# WVR_V1.net
KiCad netlist of a schematic drawn in EasyEDA
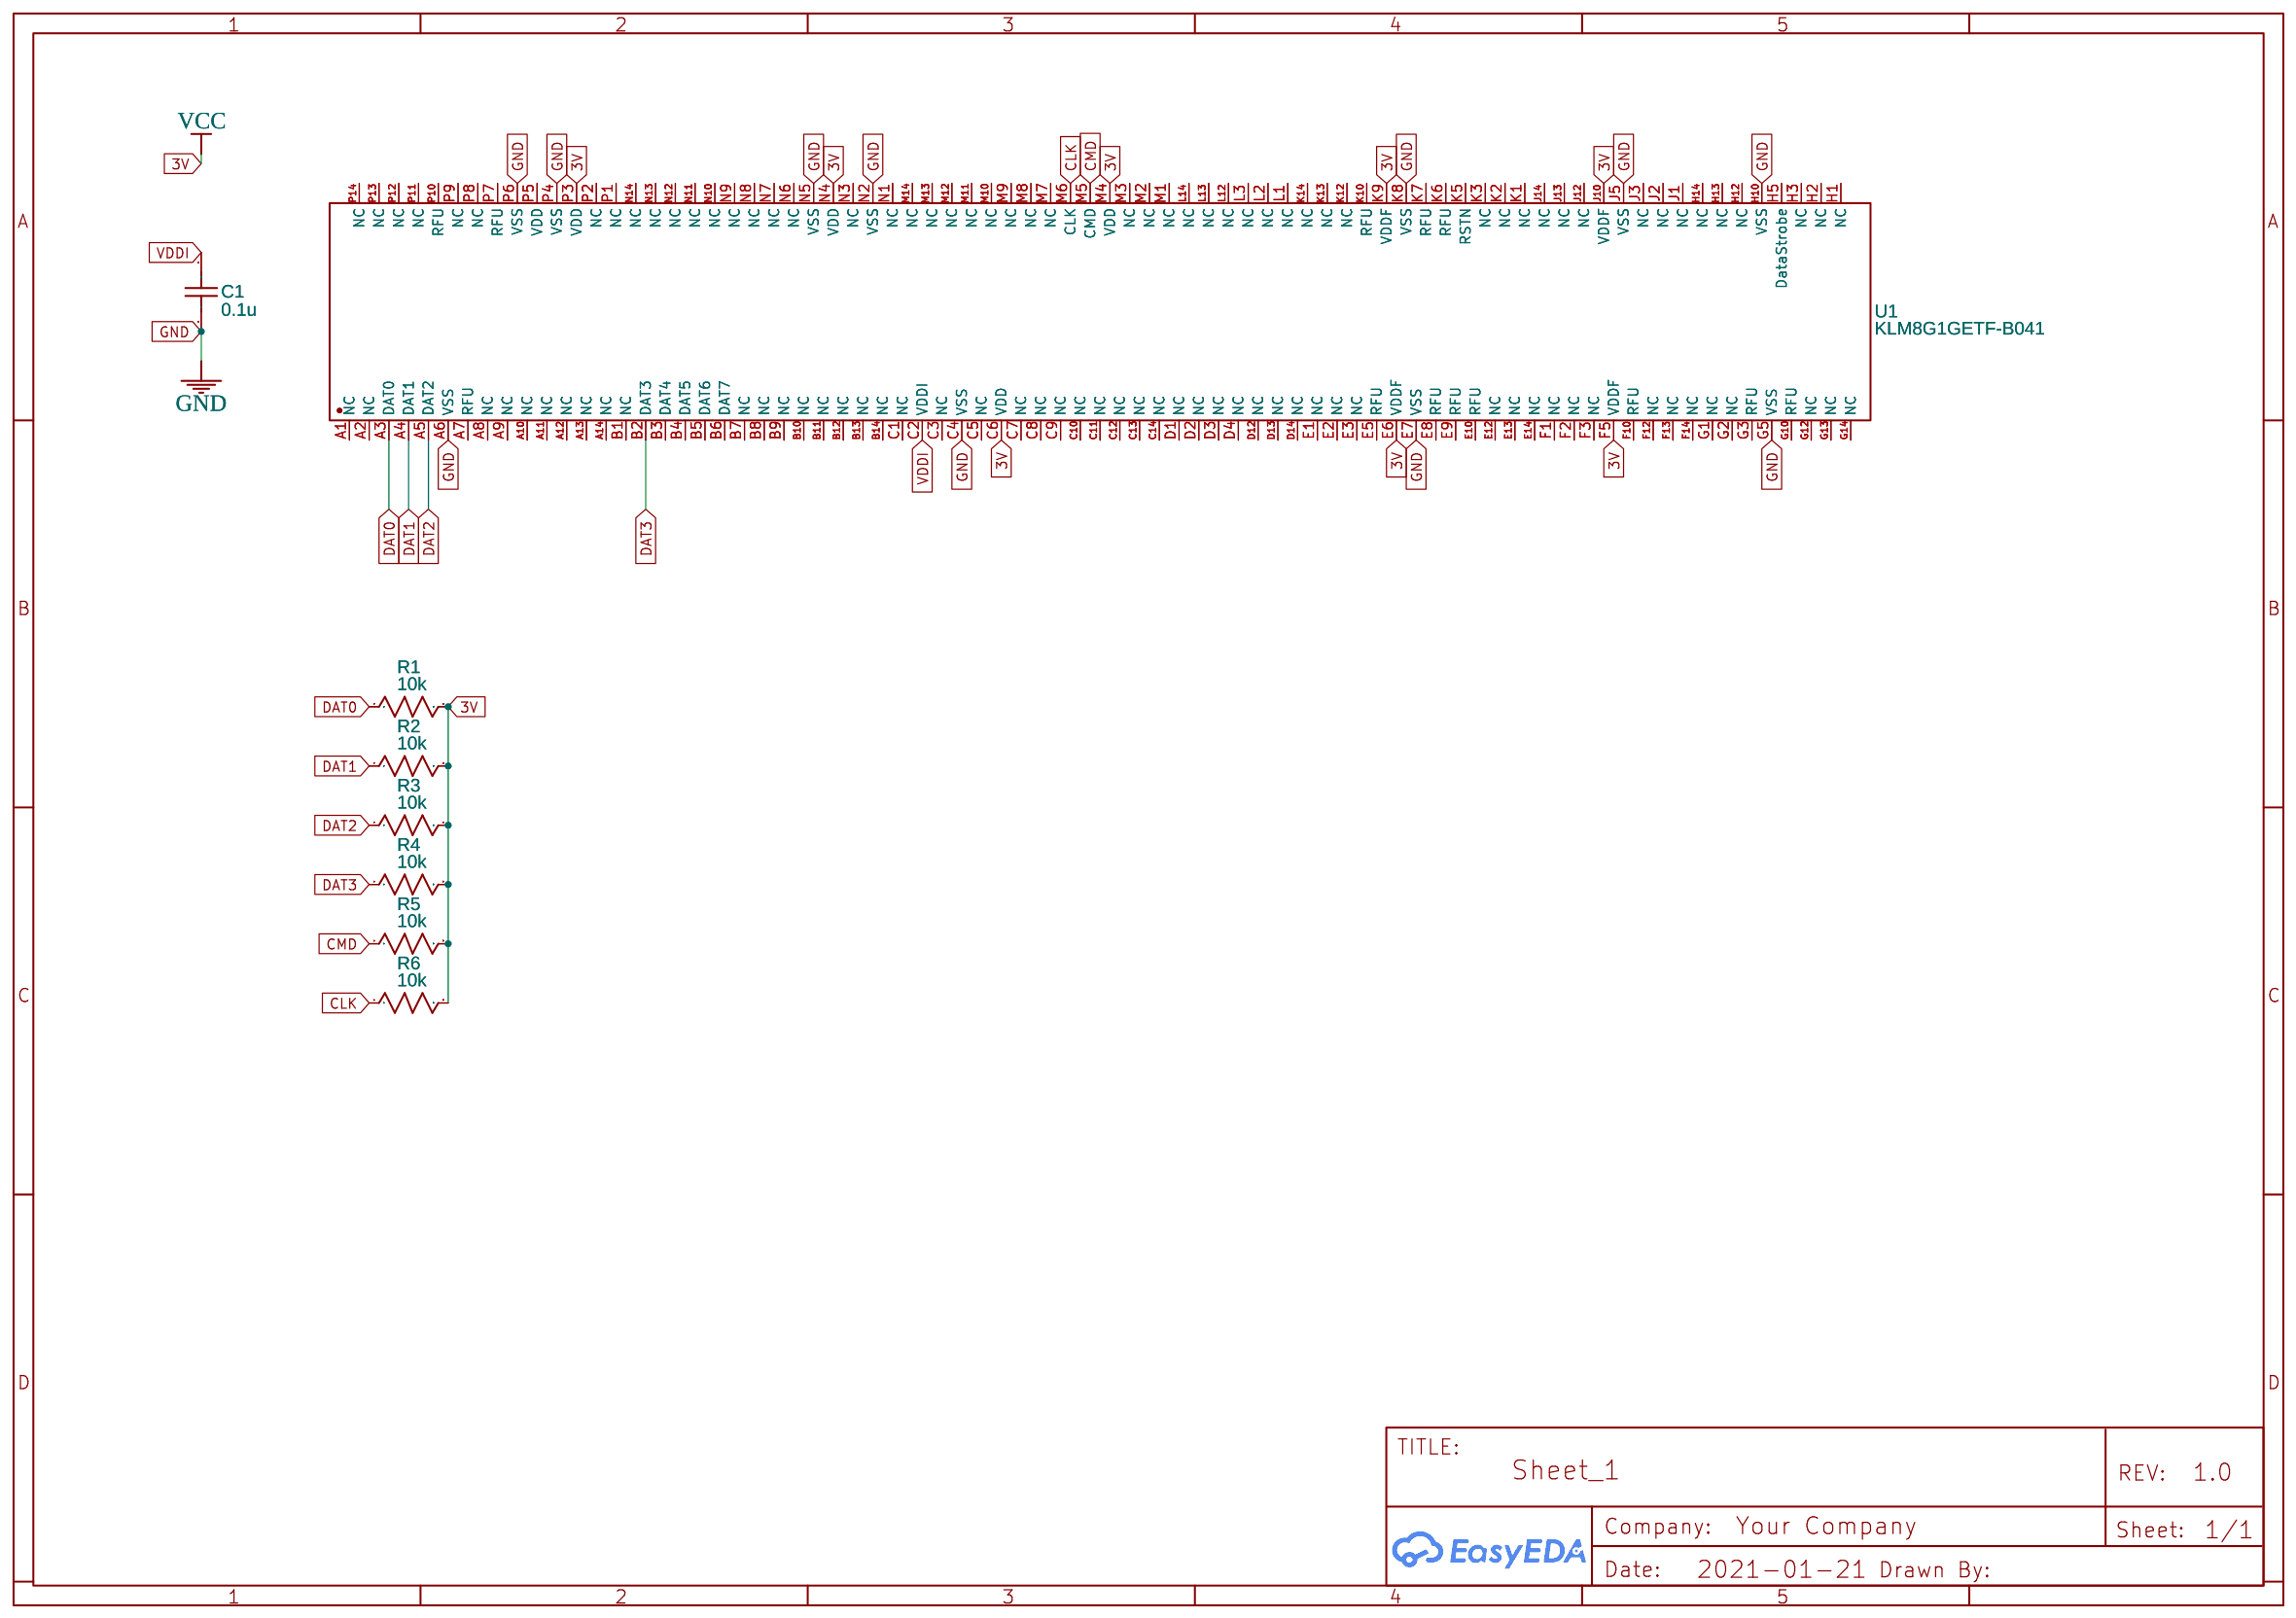
[diagram p0: schematic sheet]

(export (version "E")
  (design (tool "Eeschema 10.0.6"))
  (components
    (comp (ref "C1") (value "0.1u") (libsource (lib "") (part "C_0402_US")))
    (comp (ref "R1") (value "10k") (libsource (lib "") (part "R_0402_US")))
    (comp (ref "R2") (value "10k") (libsource (lib "") (part "R_0402_US")))
    (comp (ref "R3") (value "10k") (libsource (lib "") (part "R_0402_US")))
    (comp (ref "R4") (value "10k") (libsource (lib "") (part "R_0402_US")))
    (comp (ref "R5") (value "10k") (libsource (lib "") (part "R_0402_US")))
    (comp (ref "R6") (value "10k") (libsource (lib "") (part "R_0402_US")))
    (comp (ref "U1")
      (value "KLM8G1GETF-B041")
      (fields (field (name "BOM_Supplier Part") "C499918"))
      (libsource (lib "") (part "KLM8G1GETF-B041"))
    )
  )
  (nets
    (net (code "1") (name "3V") (class "Default")
      (node (ref "R1") (pin "2") (pinfunction "2_2") (pintype "unspecified"))
      (node (ref "R2") (pin "2") (pinfunction "2_2") (pintype "unspecified"))
      (node (ref "R3") (pin "2") (pinfunction "2_2") (pintype "unspecified"))
      (node (ref "R4") (pin "2") (pinfunction "2_2") (pintype "unspecified"))
      (node (ref "R5") (pin "2") (pinfunction "2_2") (pintype "unspecified"))
      (node (ref "R6") (pin "2") (pinfunction "2_2") (pintype "unspecified"))
      (node (ref "U1") (pin "C6") (pinfunction "VDD_C6") (pintype "unspecified"))
      (node (ref "U1") (pin "E6") (pinfunction "VDDF_E6") (pintype "unspecified"))
      (node (ref "U1") (pin "F5") (pinfunction "VDDF_F5") (pintype "unspecified"))
      (node (ref "U1") (pin "J10") (pinfunction "VDDF_J10") (pintype "unspecified"))
      (node (ref "U1") (pin "K9") (pinfunction "VDDF_K9") (pintype "unspecified"))
      (node (ref "U1") (pin "M4") (pinfunction "VDD_M4") (pintype "unspecified"))
      (node (ref "U1") (pin "N4") (pinfunction "VDD_N4") (pintype "unspecified"))
      (node (ref "U1") (pin "P3") (pinfunction "VDD_P3") (pintype "unspecified"))
    )
    (net (code "2") (name "CLK") (class "Default")
      (node (ref "R6") (pin "1") (pinfunction "1_1") (pintype "unspecified"))
      (node (ref "U1") (pin "M6") (pinfunction "CLK_M6") (pintype "unspecified"))
    )
    (net (code "3") (name "CMD") (class "Default")
      (node (ref "R5") (pin "1") (pinfunction "1_1") (pintype "unspecified"))
      (node (ref "U1") (pin "M5") (pinfunction "CMD_M5") (pintype "unspecified"))
    )
    (net (code "4") (name "DAT0") (class "Default")
      (node (ref "R1") (pin "1") (pinfunction "1_1") (pintype "unspecified"))
      (node (ref "U1") (pin "A3") (pinfunction "DAT0_A3") (pintype "unspecified"))
    )
    (net (code "5") (name "DAT1") (class "Default")
      (node (ref "R2") (pin "1") (pinfunction "1_1") (pintype "unspecified"))
      (node (ref "U1") (pin "A4") (pinfunction "DAT1_A4") (pintype "unspecified"))
    )
    (net (code "6") (name "DAT2") (class "Default")
      (node (ref "R3") (pin "1") (pinfunction "1_1") (pintype "unspecified"))
      (node (ref "U1") (pin "A5") (pinfunction "DAT2_A5") (pintype "unspecified"))
    )
    (net (code "7") (name "DAT3") (class "Default")
      (node (ref "R4") (pin "1") (pinfunction "1_1") (pintype "unspecified"))
      (node (ref "U1") (pin "B2") (pinfunction "DAT3_B2") (pintype "unspecified"))
    )
    (net (code "8") (name "GND") (class "Default")
      (node (ref "C1") (pin "1") (pinfunction "1_1") (pintype "unspecified"))
      (node (ref "U1") (pin "A6") (pinfunction "VSS_A6") (pintype "unspecified"))
      (node (ref "U1") (pin "C4") (pinfunction "VSS_C4") (pintype "unspecified"))
      (node (ref "U1") (pin "E7") (pinfunction "VSS_E7") (pintype "unspecified"))
      (node (ref "U1") (pin "G5") (pinfunction "VSS_G5") (pintype "unspecified"))
      (node (ref "U1") (pin "H10") (pinfunction "VSS_H10") (pintype "unspecified"))
      (node (ref "U1") (pin "J5") (pinfunction "VSS_J5") (pintype "unspecified"))
      (node (ref "U1") (pin "K8") (pinfunction "VSS_K8") (pintype "unspecified"))
      (node (ref "U1") (pin "N2") (pinfunction "VSS_N2") (pintype "unspecified"))
      (node (ref "U1") (pin "N5") (pinfunction "VSS_N5") (pintype "unspecified"))
      (node (ref "U1") (pin "P4") (pinfunction "VSS_P4") (pintype "unspecified"))
      (node (ref "U1") (pin "P6") (pinfunction "VSS_P6") (pintype "unspecified"))
    )
    (net (code "9") (name "VDDI") (class "Default")
      (node (ref "C1") (pin "2") (pinfunction "2_2") (pintype "unspecified"))
      (node (ref "U1") (pin "C2") (pinfunction "VDDI_C2") (pintype "unspecified"))
    )
    (net (code "10") (name "unconnected-(U1-DAT4-PadB3)") (class "Default")
      (node (ref "U1") (pin "B3") (pinfunction "DAT4_B3") (pintype "unspecified"))
    )
    (net (code "11") (name "unconnected-(U1-DAT5-PadB4)") (class "Default")
      (node (ref "U1") (pin "B4") (pinfunction "DAT5_B4") (pintype "unspecified"))
    )
    (net (code "12") (name "unconnected-(U1-DAT6-PadB5)") (class "Default")
      (node (ref "U1") (pin "B5") (pinfunction "DAT6_B5") (pintype "unspecified"))
    )
    (net (code "13") (name "unconnected-(U1-DAT7-PadB6)") (class "Default")
      (node (ref "U1") (pin "B6") (pinfunction "DAT7_B6") (pintype "unspecified"))
    )
    (net (code "14") (name "unconnected-(U1-DataStrobe-PadH5)") (class "Default")
      (node (ref "U1") (pin "H5") (pinfunction "DataStrobe_H5") (pintype "unspecified"))
    )
    (net (code "15") (name "unconnected-(U1-NC-PadA1)") (class "Default")
      (node (ref "U1") (pin "A1") (pinfunction "NC_A1") (pintype "unspecified"))
    )
    (net (code "16") (name "unconnected-(U1-NC-PadA2)") (class "Default")
      (node (ref "U1") (pin "A2") (pinfunction "NC_A2") (pintype "unspecified"))
    )
    (net (code "17") (name "unconnected-(U1-NC-PadA8)") (class "Default")
      (node (ref "U1") (pin "A8") (pinfunction "NC_A8") (pintype "unspecified"))
    )
    (net (code "18") (name "unconnected-(U1-NC-PadA9)") (class "Default")
      (node (ref "U1") (pin "A9") (pinfunction "NC_A9") (pintype "unspecified"))
    )
    (net (code "19") (name "unconnected-(U1-NC-PadA10)") (class "Default")
      (node (ref "U1") (pin "A10") (pinfunction "NC_A10") (pintype "unspecified"))
    )
    (net (code "20") (name "unconnected-(U1-NC-PadA11)") (class "Default")
      (node (ref "U1") (pin "A11") (pinfunction "NC_A11") (pintype "unspecified"))
    )
    (net (code "21") (name "unconnected-(U1-NC-PadA12)") (class "Default")
      (node (ref "U1") (pin "A12") (pinfunction "NC_A12") (pintype "unspecified"))
    )
    (net (code "22") (name "unconnected-(U1-NC-PadA13)") (class "Default")
      (node (ref "U1") (pin "A13") (pinfunction "NC_A13") (pintype "unspecified"))
    )
    (net (code "23") (name "unconnected-(U1-NC-PadA14)") (class "Default")
      (node (ref "U1") (pin "A14") (pinfunction "NC_A14") (pintype "unspecified"))
    )
    (net (code "24") (name "unconnected-(U1-NC-PadB1)") (class "Default")
      (node (ref "U1") (pin "B1") (pinfunction "NC_B1") (pintype "unspecified"))
    )
    (net (code "25") (name "unconnected-(U1-NC-PadB7)") (class "Default")
      (node (ref "U1") (pin "B7") (pinfunction "NC_B7") (pintype "unspecified"))
    )
    (net (code "26") (name "unconnected-(U1-NC-PadB8)") (class "Default")
      (node (ref "U1") (pin "B8") (pinfunction "NC_B8") (pintype "unspecified"))
    )
    (net (code "27") (name "unconnected-(U1-NC-PadB9)") (class "Default")
      (node (ref "U1") (pin "B9") (pinfunction "NC_B9") (pintype "unspecified"))
    )
    (net (code "28") (name "unconnected-(U1-NC-PadB10)") (class "Default")
      (node (ref "U1") (pin "B10") (pinfunction "NC_B10") (pintype "unspecified"))
    )
    (net (code "29") (name "unconnected-(U1-NC-PadB11)") (class "Default")
      (node (ref "U1") (pin "B11") (pinfunction "NC_B11") (pintype "unspecified"))
    )
    (net (code "30") (name "unconnected-(U1-NC-PadB12)") (class "Default")
      (node (ref "U1") (pin "B12") (pinfunction "NC_B12") (pintype "unspecified"))
    )
    (net (code "31") (name "unconnected-(U1-NC-PadB13)") (class "Default")
      (node (ref "U1") (pin "B13") (pinfunction "NC_B13") (pintype "unspecified"))
    )
    (net (code "32") (name "unconnected-(U1-NC-PadB14)") (class "Default")
      (node (ref "U1") (pin "B14") (pinfunction "NC_B14") (pintype "unspecified"))
    )
    (net (code "33") (name "unconnected-(U1-NC-PadC1)") (class "Default")
      (node (ref "U1") (pin "C1") (pinfunction "NC_C1") (pintype "unspecified"))
    )
    (net (code "34") (name "unconnected-(U1-NC-PadC3)") (class "Default")
      (node (ref "U1") (pin "C3") (pinfunction "NC_C3") (pintype "unspecified"))
    )
    (net (code "35") (name "unconnected-(U1-NC-PadC5)") (class "Default")
      (node (ref "U1") (pin "C5") (pinfunction "NC_C5") (pintype "unspecified"))
    )
    (net (code "36") (name "unconnected-(U1-NC-PadC7)") (class "Default")
      (node (ref "U1") (pin "C7") (pinfunction "NC_C7") (pintype "unspecified"))
    )
    (net (code "37") (name "unconnected-(U1-NC-PadC8)") (class "Default")
      (node (ref "U1") (pin "C8") (pinfunction "NC_C8") (pintype "unspecified"))
    )
    (net (code "38") (name "unconnected-(U1-NC-PadC9)") (class "Default")
      (node (ref "U1") (pin "C9") (pinfunction "NC_C9") (pintype "unspecified"))
    )
    (net (code "39") (name "unconnected-(U1-NC-PadC10)") (class "Default")
      (node (ref "U1") (pin "C10") (pinfunction "NC_C10") (pintype "unspecified"))
    )
    (net (code "40") (name "unconnected-(U1-NC-PadC11)") (class "Default")
      (node (ref "U1") (pin "C11") (pinfunction "NC_C11") (pintype "unspecified"))
    )
    (net (code "41") (name "unconnected-(U1-NC-PadC12)") (class "Default")
      (node (ref "U1") (pin "C12") (pinfunction "NC_C12") (pintype "unspecified"))
    )
    (net (code "42") (name "unconnected-(U1-NC-PadC13)") (class "Default")
      (node (ref "U1") (pin "C13") (pinfunction "NC_C13") (pintype "unspecified"))
    )
    (net (code "43") (name "unconnected-(U1-NC-PadC14)") (class "Default")
      (node (ref "U1") (pin "C14") (pinfunction "NC_C14") (pintype "unspecified"))
    )
    (net (code "44") (name "unconnected-(U1-NC-PadD1)") (class "Default")
      (node (ref "U1") (pin "D1") (pinfunction "NC_D1") (pintype "unspecified"))
    )
    (net (code "45") (name "unconnected-(U1-NC-PadD2)") (class "Default")
      (node (ref "U1") (pin "D2") (pinfunction "NC_D2") (pintype "unspecified"))
    )
    (net (code "46") (name "unconnected-(U1-NC-PadD3)") (class "Default")
      (node (ref "U1") (pin "D3") (pinfunction "NC_D3") (pintype "unspecified"))
    )
    (net (code "47") (name "unconnected-(U1-NC-PadD4)") (class "Default")
      (node (ref "U1") (pin "D4") (pinfunction "NC_D4") (pintype "unspecified"))
    )
    (net (code "48") (name "unconnected-(U1-NC-PadD12)") (class "Default")
      (node (ref "U1") (pin "D12") (pinfunction "NC_D12") (pintype "unspecified"))
    )
    (net (code "49") (name "unconnected-(U1-NC-PadD13)") (class "Default")
      (node (ref "U1") (pin "D13") (pinfunction "NC_D13") (pintype "unspecified"))
    )
    (net (code "50") (name "unconnected-(U1-NC-PadD14)") (class "Default")
      (node (ref "U1") (pin "D14") (pinfunction "NC_D14") (pintype "unspecified"))
    )
    (net (code "51") (name "unconnected-(U1-NC-PadE1)") (class "Default")
      (node (ref "U1") (pin "E1") (pinfunction "NC_E1") (pintype "unspecified"))
    )
    (net (code "52") (name "unconnected-(U1-NC-PadE2)") (class "Default")
      (node (ref "U1") (pin "E2") (pinfunction "NC_E2") (pintype "unspecified"))
    )
    (net (code "53") (name "unconnected-(U1-NC-PadE3)") (class "Default")
      (node (ref "U1") (pin "E3") (pinfunction "NC_E3") (pintype "unspecified"))
    )
    (net (code "54") (name "unconnected-(U1-NC-PadE12)") (class "Default")
      (node (ref "U1") (pin "E12") (pinfunction "NC_E12") (pintype "unspecified"))
    )
    (net (code "55") (name "unconnected-(U1-NC-PadE13)") (class "Default")
      (node (ref "U1") (pin "E13") (pinfunction "NC_E13") (pintype "unspecified"))
    )
    (net (code "56") (name "unconnected-(U1-NC-PadE14)") (class "Default")
      (node (ref "U1") (pin "E14") (pinfunction "NC_E14") (pintype "unspecified"))
    )
    (net (code "57") (name "unconnected-(U1-NC-PadF1)") (class "Default")
      (node (ref "U1") (pin "F1") (pinfunction "NC_F1") (pintype "unspecified"))
    )
    (net (code "58") (name "unconnected-(U1-NC-PadF2)") (class "Default")
      (node (ref "U1") (pin "F2") (pinfunction "NC_F2") (pintype "unspecified"))
    )
    (net (code "59") (name "unconnected-(U1-NC-PadF3)") (class "Default")
      (node (ref "U1") (pin "F3") (pinfunction "NC_F3") (pintype "unspecified"))
    )
    (net (code "60") (name "unconnected-(U1-NC-PadF12)") (class "Default")
      (node (ref "U1") (pin "F12") (pinfunction "NC_F12") (pintype "unspecified"))
    )
    (net (code "61") (name "unconnected-(U1-NC-PadF13)") (class "Default")
      (node (ref "U1") (pin "F13") (pinfunction "NC_F13") (pintype "unspecified"))
    )
    (net (code "62") (name "unconnected-(U1-NC-PadF14)") (class "Default")
      (node (ref "U1") (pin "F14") (pinfunction "NC_F14") (pintype "unspecified"))
    )
    (net (code "63") (name "unconnected-(U1-NC-PadG1)") (class "Default")
      (node (ref "U1") (pin "G1") (pinfunction "NC_G1") (pintype "unspecified"))
    )
    (net (code "64") (name "unconnected-(U1-NC-PadG2)") (class "Default")
      (node (ref "U1") (pin "G2") (pinfunction "NC_G2") (pintype "unspecified"))
    )
    (net (code "65") (name "unconnected-(U1-NC-PadG12)") (class "Default")
      (node (ref "U1") (pin "G12") (pinfunction "NC_G12") (pintype "unspecified"))
    )
    (net (code "66") (name "unconnected-(U1-NC-PadG13)") (class "Default")
      (node (ref "U1") (pin "G13") (pinfunction "NC_G13") (pintype "unspecified"))
    )
    (net (code "67") (name "unconnected-(U1-NC-PadG14)") (class "Default")
      (node (ref "U1") (pin "G14") (pinfunction "NC_G14") (pintype "unspecified"))
    )
    (net (code "68") (name "unconnected-(U1-NC-PadH1)") (class "Default")
      (node (ref "U1") (pin "H1") (pinfunction "NC_H1") (pintype "unspecified"))
    )
    (net (code "69") (name "unconnected-(U1-NC-PadH2)") (class "Default")
      (node (ref "U1") (pin "H2") (pinfunction "NC_H2") (pintype "unspecified"))
    )
    (net (code "70") (name "unconnected-(U1-NC-PadH3)") (class "Default")
      (node (ref "U1") (pin "H3") (pinfunction "NC_H3") (pintype "unspecified"))
    )
    (net (code "71") (name "unconnected-(U1-NC-PadH12)") (class "Default")
      (node (ref "U1") (pin "H12") (pinfunction "NC_H12") (pintype "unspecified"))
    )
    (net (code "72") (name "unconnected-(U1-NC-PadH13)") (class "Default")
      (node (ref "U1") (pin "H13") (pinfunction "NC_H13") (pintype "unspecified"))
    )
    (net (code "73") (name "unconnected-(U1-NC-PadH14)") (class "Default")
      (node (ref "U1") (pin "H14") (pinfunction "NC_H14") (pintype "unspecified"))
    )
    (net (code "74") (name "unconnected-(U1-NC-PadJ1)") (class "Default")
      (node (ref "U1") (pin "J1") (pinfunction "NC_J1") (pintype "unspecified"))
    )
    (net (code "75") (name "unconnected-(U1-NC-PadJ2)") (class "Default")
      (node (ref "U1") (pin "J2") (pinfunction "NC_J2") (pintype "unspecified"))
    )
    (net (code "76") (name "unconnected-(U1-NC-PadJ3)") (class "Default")
      (node (ref "U1") (pin "J3") (pinfunction "NC_J3") (pintype "unspecified"))
    )
    (net (code "77") (name "unconnected-(U1-NC-PadJ12)") (class "Default")
      (node (ref "U1") (pin "J12") (pinfunction "NC_J12") (pintype "unspecified"))
    )
    (net (code "78") (name "unconnected-(U1-NC-PadJ13)") (class "Default")
      (node (ref "U1") (pin "J13") (pinfunction "NC_J13") (pintype "unspecified"))
    )
    (net (code "79") (name "unconnected-(U1-NC-PadJ14)") (class "Default")
      (node (ref "U1") (pin "J14") (pinfunction "NC_J14") (pintype "unspecified"))
    )
    (net (code "80") (name "unconnected-(U1-NC-PadK1)") (class "Default")
      (node (ref "U1") (pin "K1") (pinfunction "NC_K1") (pintype "unspecified"))
    )
    (net (code "81") (name "unconnected-(U1-NC-PadK2)") (class "Default")
      (node (ref "U1") (pin "K2") (pinfunction "NC_K2") (pintype "unspecified"))
    )
    (net (code "82") (name "unconnected-(U1-NC-PadK3)") (class "Default")
      (node (ref "U1") (pin "K3") (pinfunction "NC_K3") (pintype "unspecified"))
    )
    (net (code "83") (name "unconnected-(U1-NC-PadK12)") (class "Default")
      (node (ref "U1") (pin "K12") (pinfunction "NC_K12") (pintype "unspecified"))
    )
    (net (code "84") (name "unconnected-(U1-NC-PadK13)") (class "Default")
      (node (ref "U1") (pin "K13") (pinfunction "NC_K13") (pintype "unspecified"))
    )
    (net (code "85") (name "unconnected-(U1-NC-PadK14)") (class "Default")
      (node (ref "U1") (pin "K14") (pinfunction "NC_K14") (pintype "unspecified"))
    )
    (net (code "86") (name "unconnected-(U1-NC-PadL1)") (class "Default")
      (node (ref "U1") (pin "L1") (pinfunction "NC_L1") (pintype "unspecified"))
    )
    (net (code "87") (name "unconnected-(U1-NC-PadL2)") (class "Default")
      (node (ref "U1") (pin "L2") (pinfunction "NC_L2") (pintype "unspecified"))
    )
    (net (code "88") (name "unconnected-(U1-NC-PadL3)") (class "Default")
      (node (ref "U1") (pin "L3") (pinfunction "NC_L3") (pintype "unspecified"))
    )
    (net (code "89") (name "unconnected-(U1-NC-PadL12)") (class "Default")
      (node (ref "U1") (pin "L12") (pinfunction "NC_L12") (pintype "unspecified"))
    )
    (net (code "90") (name "unconnected-(U1-NC-PadL13)") (class "Default")
      (node (ref "U1") (pin "L13") (pinfunction "NC_L13") (pintype "unspecified"))
    )
    (net (code "91") (name "unconnected-(U1-NC-PadL14)") (class "Default")
      (node (ref "U1") (pin "L14") (pinfunction "NC_L14") (pintype "unspecified"))
    )
    (net (code "92") (name "unconnected-(U1-NC-PadM1)") (class "Default")
      (node (ref "U1") (pin "M1") (pinfunction "NC_M1") (pintype "unspecified"))
    )
    (net (code "93") (name "unconnected-(U1-NC-PadM2)") (class "Default")
      (node (ref "U1") (pin "M2") (pinfunction "NC_M2") (pintype "unspecified"))
    )
    (net (code "94") (name "unconnected-(U1-NC-PadM3)") (class "Default")
      (node (ref "U1") (pin "M3") (pinfunction "NC_M3") (pintype "unspecified"))
    )
    (net (code "95") (name "unconnected-(U1-NC-PadM7)") (class "Default")
      (node (ref "U1") (pin "M7") (pinfunction "NC_M7") (pintype "unspecified"))
    )
    (net (code "96") (name "unconnected-(U1-NC-PadM8)") (class "Default")
      (node (ref "U1") (pin "M8") (pinfunction "NC_M8") (pintype "unspecified"))
    )
    (net (code "97") (name "unconnected-(U1-NC-PadM9)") (class "Default")
      (node (ref "U1") (pin "M9") (pinfunction "NC_M9") (pintype "unspecified"))
    )
    (net (code "98") (name "unconnected-(U1-NC-PadM10)") (class "Default")
      (node (ref "U1") (pin "M10") (pinfunction "NC_M10") (pintype "unspecified"))
    )
    (net (code "99") (name "unconnected-(U1-NC-PadM11)") (class "Default")
      (node (ref "U1") (pin "M11") (pinfunction "NC_M11") (pintype "unspecified"))
    )
    (net (code "100") (name "unconnected-(U1-NC-PadM12)") (class "Default")
      (node (ref "U1") (pin "M12") (pinfunction "NC_M12") (pintype "unspecified"))
    )
    (net (code "101") (name "unconnected-(U1-NC-PadM13)") (class "Default")
      (node (ref "U1") (pin "M13") (pinfunction "NC_M13") (pintype "unspecified"))
    )
    (net (code "102") (name "unconnected-(U1-NC-PadM14)") (class "Default")
      (node (ref "U1") (pin "M14") (pinfunction "NC_M14") (pintype "unspecified"))
    )
    (net (code "103") (name "unconnected-(U1-NC-PadN1)") (class "Default")
      (node (ref "U1") (pin "N1") (pinfunction "NC_N1") (pintype "unspecified"))
    )
    (net (code "104") (name "unconnected-(U1-NC-PadN3)") (class "Default")
      (node (ref "U1") (pin "N3") (pinfunction "NC_N3") (pintype "unspecified"))
    )
    (net (code "105") (name "unconnected-(U1-NC-PadN6)") (class "Default")
      (node (ref "U1") (pin "N6") (pinfunction "NC_N6") (pintype "unspecified"))
    )
    (net (code "106") (name "unconnected-(U1-NC-PadN7)") (class "Default")
      (node (ref "U1") (pin "N7") (pinfunction "NC_N7") (pintype "unspecified"))
    )
    (net (code "107") (name "unconnected-(U1-NC-PadN8)") (class "Default")
      (node (ref "U1") (pin "N8") (pinfunction "NC_N8") (pintype "unspecified"))
    )
    (net (code "108") (name "unconnected-(U1-NC-PadN9)") (class "Default")
      (node (ref "U1") (pin "N9") (pinfunction "NC_N9") (pintype "unspecified"))
    )
    (net (code "109") (name "unconnected-(U1-NC-PadN10)") (class "Default")
      (node (ref "U1") (pin "N10") (pinfunction "NC_N10") (pintype "unspecified"))
    )
    (net (code "110") (name "unconnected-(U1-NC-PadN11)") (class "Default")
      (node (ref "U1") (pin "N11") (pinfunction "NC_N11") (pintype "unspecified"))
    )
    (net (code "111") (name "unconnected-(U1-NC-PadN12)") (class "Default")
      (node (ref "U1") (pin "N12") (pinfunction "NC_N12") (pintype "unspecified"))
    )
    (net (code "112") (name "unconnected-(U1-NC-PadN13)") (class "Default")
      (node (ref "U1") (pin "N13") (pinfunction "NC_N13") (pintype "unspecified"))
    )
    (net (code "113") (name "unconnected-(U1-NC-PadN14)") (class "Default")
      (node (ref "U1") (pin "N14") (pinfunction "NC_N14") (pintype "unspecified"))
    )
    (net (code "114") (name "unconnected-(U1-NC-PadP1)") (class "Default")
      (node (ref "U1") (pin "P1") (pinfunction "NC_P1") (pintype "unspecified"))
    )
    (net (code "115") (name "unconnected-(U1-NC-PadP2)") (class "Default")
      (node (ref "U1") (pin "P2") (pinfunction "NC_P2") (pintype "unspecified"))
    )
    (net (code "116") (name "unconnected-(U1-NC-PadP8)") (class "Default")
      (node (ref "U1") (pin "P8") (pinfunction "NC_P8") (pintype "unspecified"))
    )
    (net (code "117") (name "unconnected-(U1-NC-PadP9)") (class "Default")
      (node (ref "U1") (pin "P9") (pinfunction "NC_P9") (pintype "unspecified"))
    )
    (net (code "118") (name "unconnected-(U1-NC-PadP11)") (class "Default")
      (node (ref "U1") (pin "P11") (pinfunction "NC_P11") (pintype "unspecified"))
    )
    (net (code "119") (name "unconnected-(U1-NC-PadP12)") (class "Default")
      (node (ref "U1") (pin "P12") (pinfunction "NC_P12") (pintype "unspecified"))
    )
    (net (code "120") (name "unconnected-(U1-NC-PadP13)") (class "Default")
      (node (ref "U1") (pin "P13") (pinfunction "NC_P13") (pintype "unspecified"))
    )
    (net (code "121") (name "unconnected-(U1-NC-PadP14)") (class "Default")
      (node (ref "U1") (pin "P14") (pinfunction "NC_P14") (pintype "unspecified"))
    )
    (net (code "122") (name "unconnected-(U1-RFU-PadA7)") (class "Default")
      (node (ref "U1") (pin "A7") (pinfunction "RFU_A7") (pintype "unspecified"))
    )
    (net (code "123") (name "unconnected-(U1-RFU-PadE5)") (class "Default")
      (node (ref "U1") (pin "E5") (pinfunction "RFU_E5") (pintype "unspecified"))
    )
    (net (code "124") (name "unconnected-(U1-RFU-PadE8)") (class "Default")
      (node (ref "U1") (pin "E8") (pinfunction "RFU_E8") (pintype "unspecified"))
    )
    (net (code "125") (name "unconnected-(U1-RFU-PadE9)") (class "Default")
      (node (ref "U1") (pin "E9") (pinfunction "RFU_E9") (pintype "unspecified"))
    )
    (net (code "126") (name "unconnected-(U1-RFU-PadE10)") (class "Default")
      (node (ref "U1") (pin "E10") (pinfunction "RFU_E10") (pintype "unspecified"))
    )
    (net (code "127") (name "unconnected-(U1-RFU-PadF10)") (class "Default")
      (node (ref "U1") (pin "F10") (pinfunction "RFU_F10") (pintype "unspecified"))
    )
    (net (code "128") (name "unconnected-(U1-RFU-PadG3)") (class "Default")
      (node (ref "U1") (pin "G3") (pinfunction "RFU_G3") (pintype "unspecified"))
    )
    (net (code "129") (name "unconnected-(U1-RFU-PadG10)") (class "Default")
      (node (ref "U1") (pin "G10") (pinfunction "RFU_G10") (pintype "unspecified"))
    )
    (net (code "130") (name "unconnected-(U1-RFU-PadK6)") (class "Default")
      (node (ref "U1") (pin "K6") (pinfunction "RFU_K6") (pintype "unspecified"))
    )
    (net (code "131") (name "unconnected-(U1-RFU-PadK7)") (class "Default")
      (node (ref "U1") (pin "K7") (pinfunction "RFU_K7") (pintype "unspecified"))
    )
    (net (code "132") (name "unconnected-(U1-RFU-PadK10)") (class "Default")
      (node (ref "U1") (pin "K10") (pinfunction "RFU_K10") (pintype "unspecified"))
    )
    (net (code "133") (name "unconnected-(U1-RFU-PadP7)") (class "Default")
      (node (ref "U1") (pin "P7") (pinfunction "RFU_P7") (pintype "unspecified"))
    )
    (net (code "134") (name "unconnected-(U1-RFU-PadP10)") (class "Default")
      (node (ref "U1") (pin "P10") (pinfunction "RFU_P10") (pintype "unspecified"))
    )
    (net (code "135") (name "unconnected-(U1-RSTN-PadK5)") (class "Default")
      (node (ref "U1") (pin "K5") (pinfunction "RSTN_K5") (pintype "unspecified"))
    )
    (net (code "136") (name "unconnected-(U1-VDD-PadP5)") (class "Default")
      (node (ref "U1") (pin "P5") (pinfunction "VDD_P5") (pintype "unspecified"))
    )
  )
)
